# SmartHelmet.net
KiCad netlist of a schematic drawn in Altium Designer
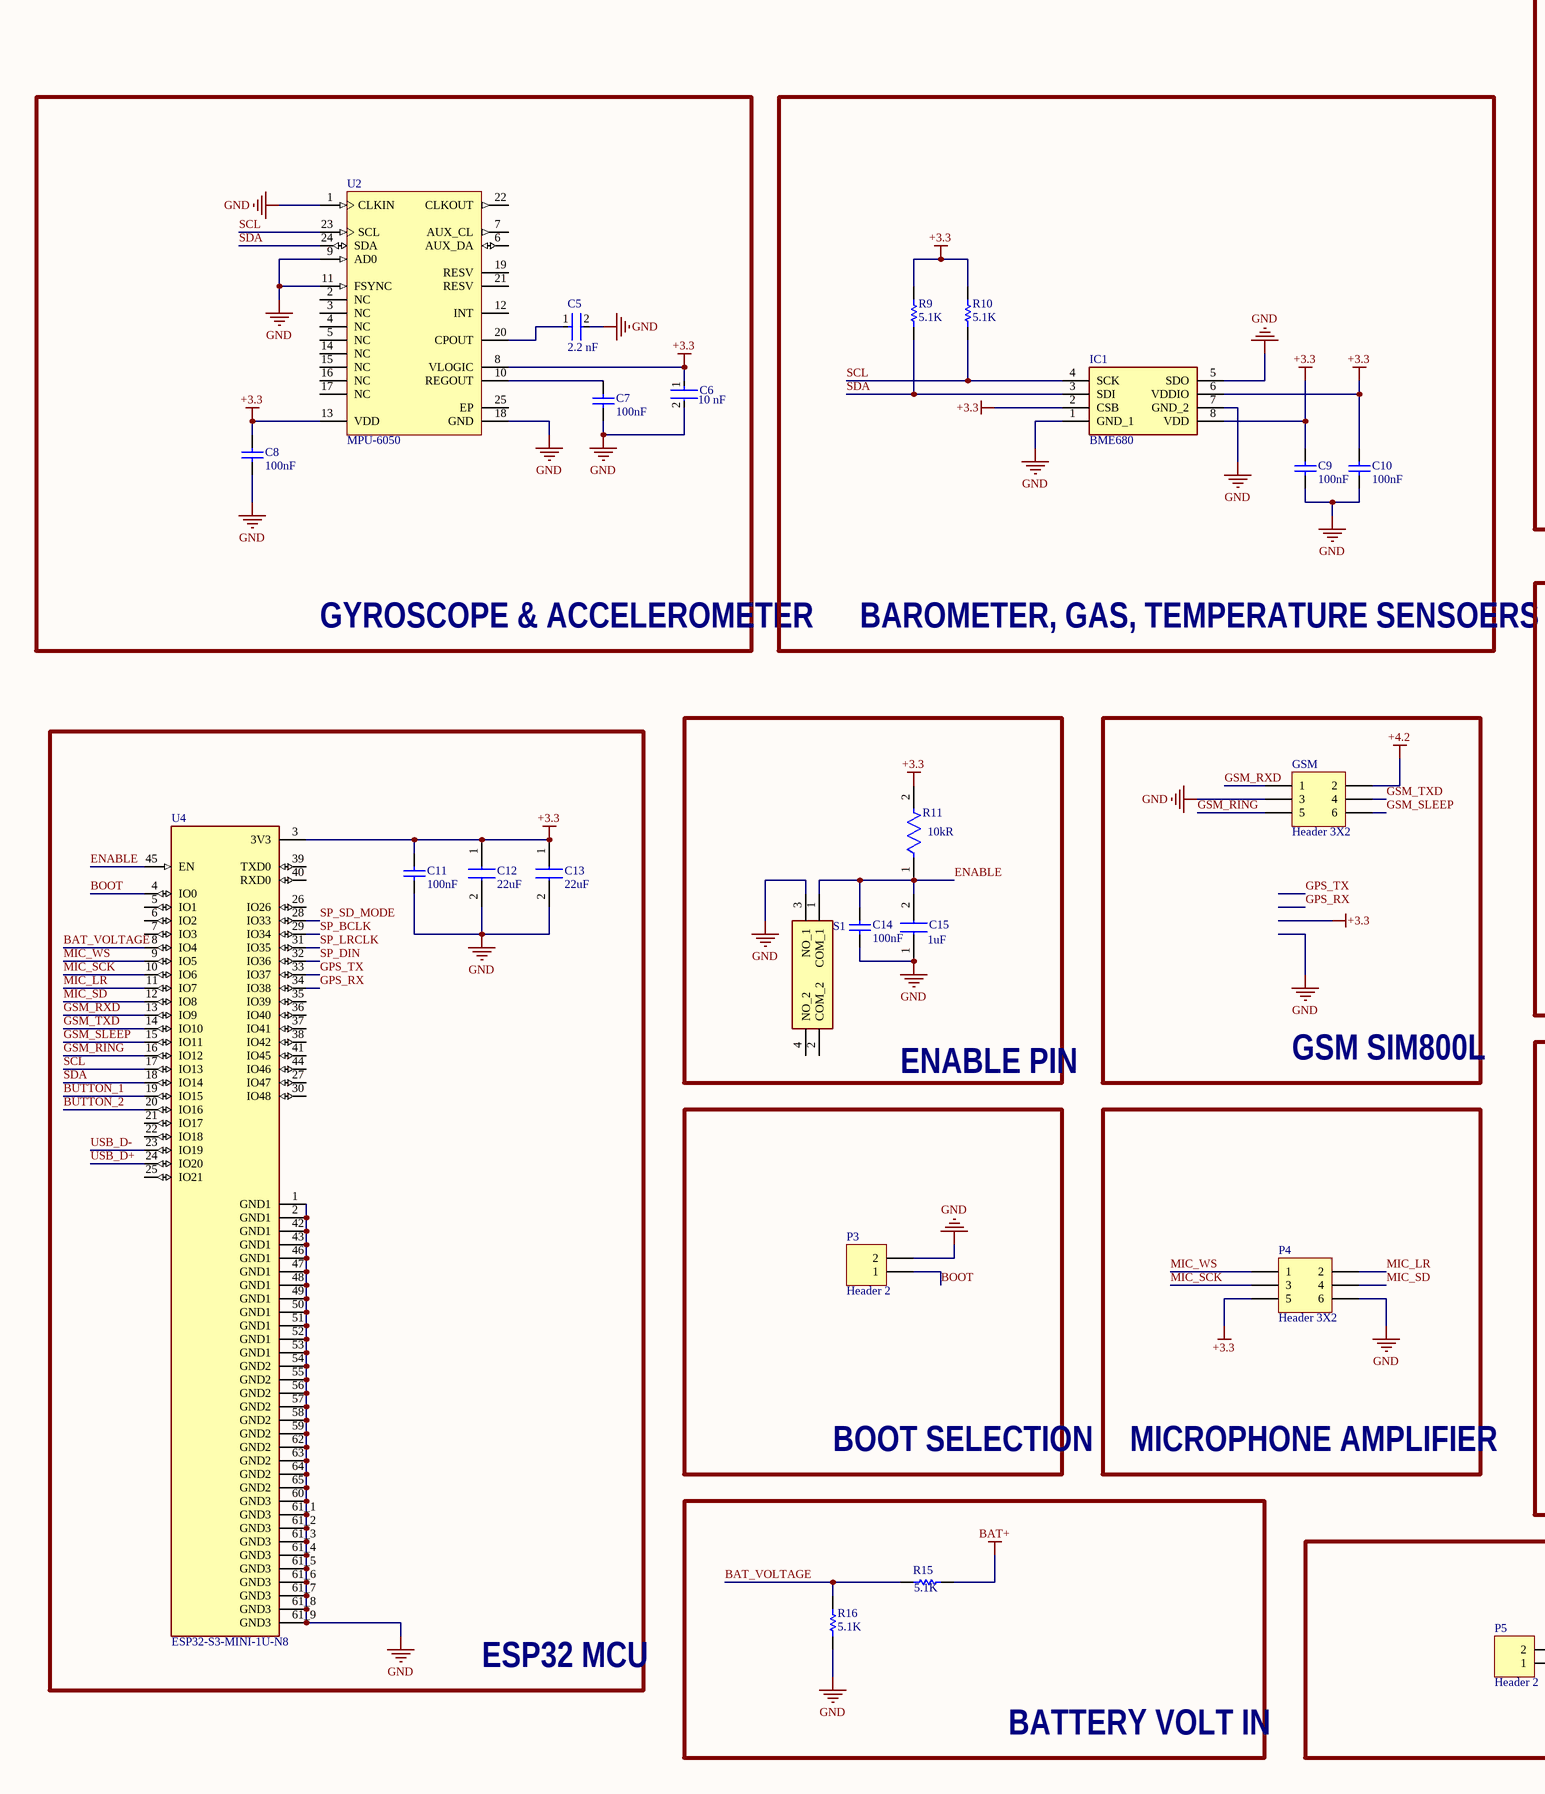
[diagram p0: SmartHelmet.SchDoc, left]
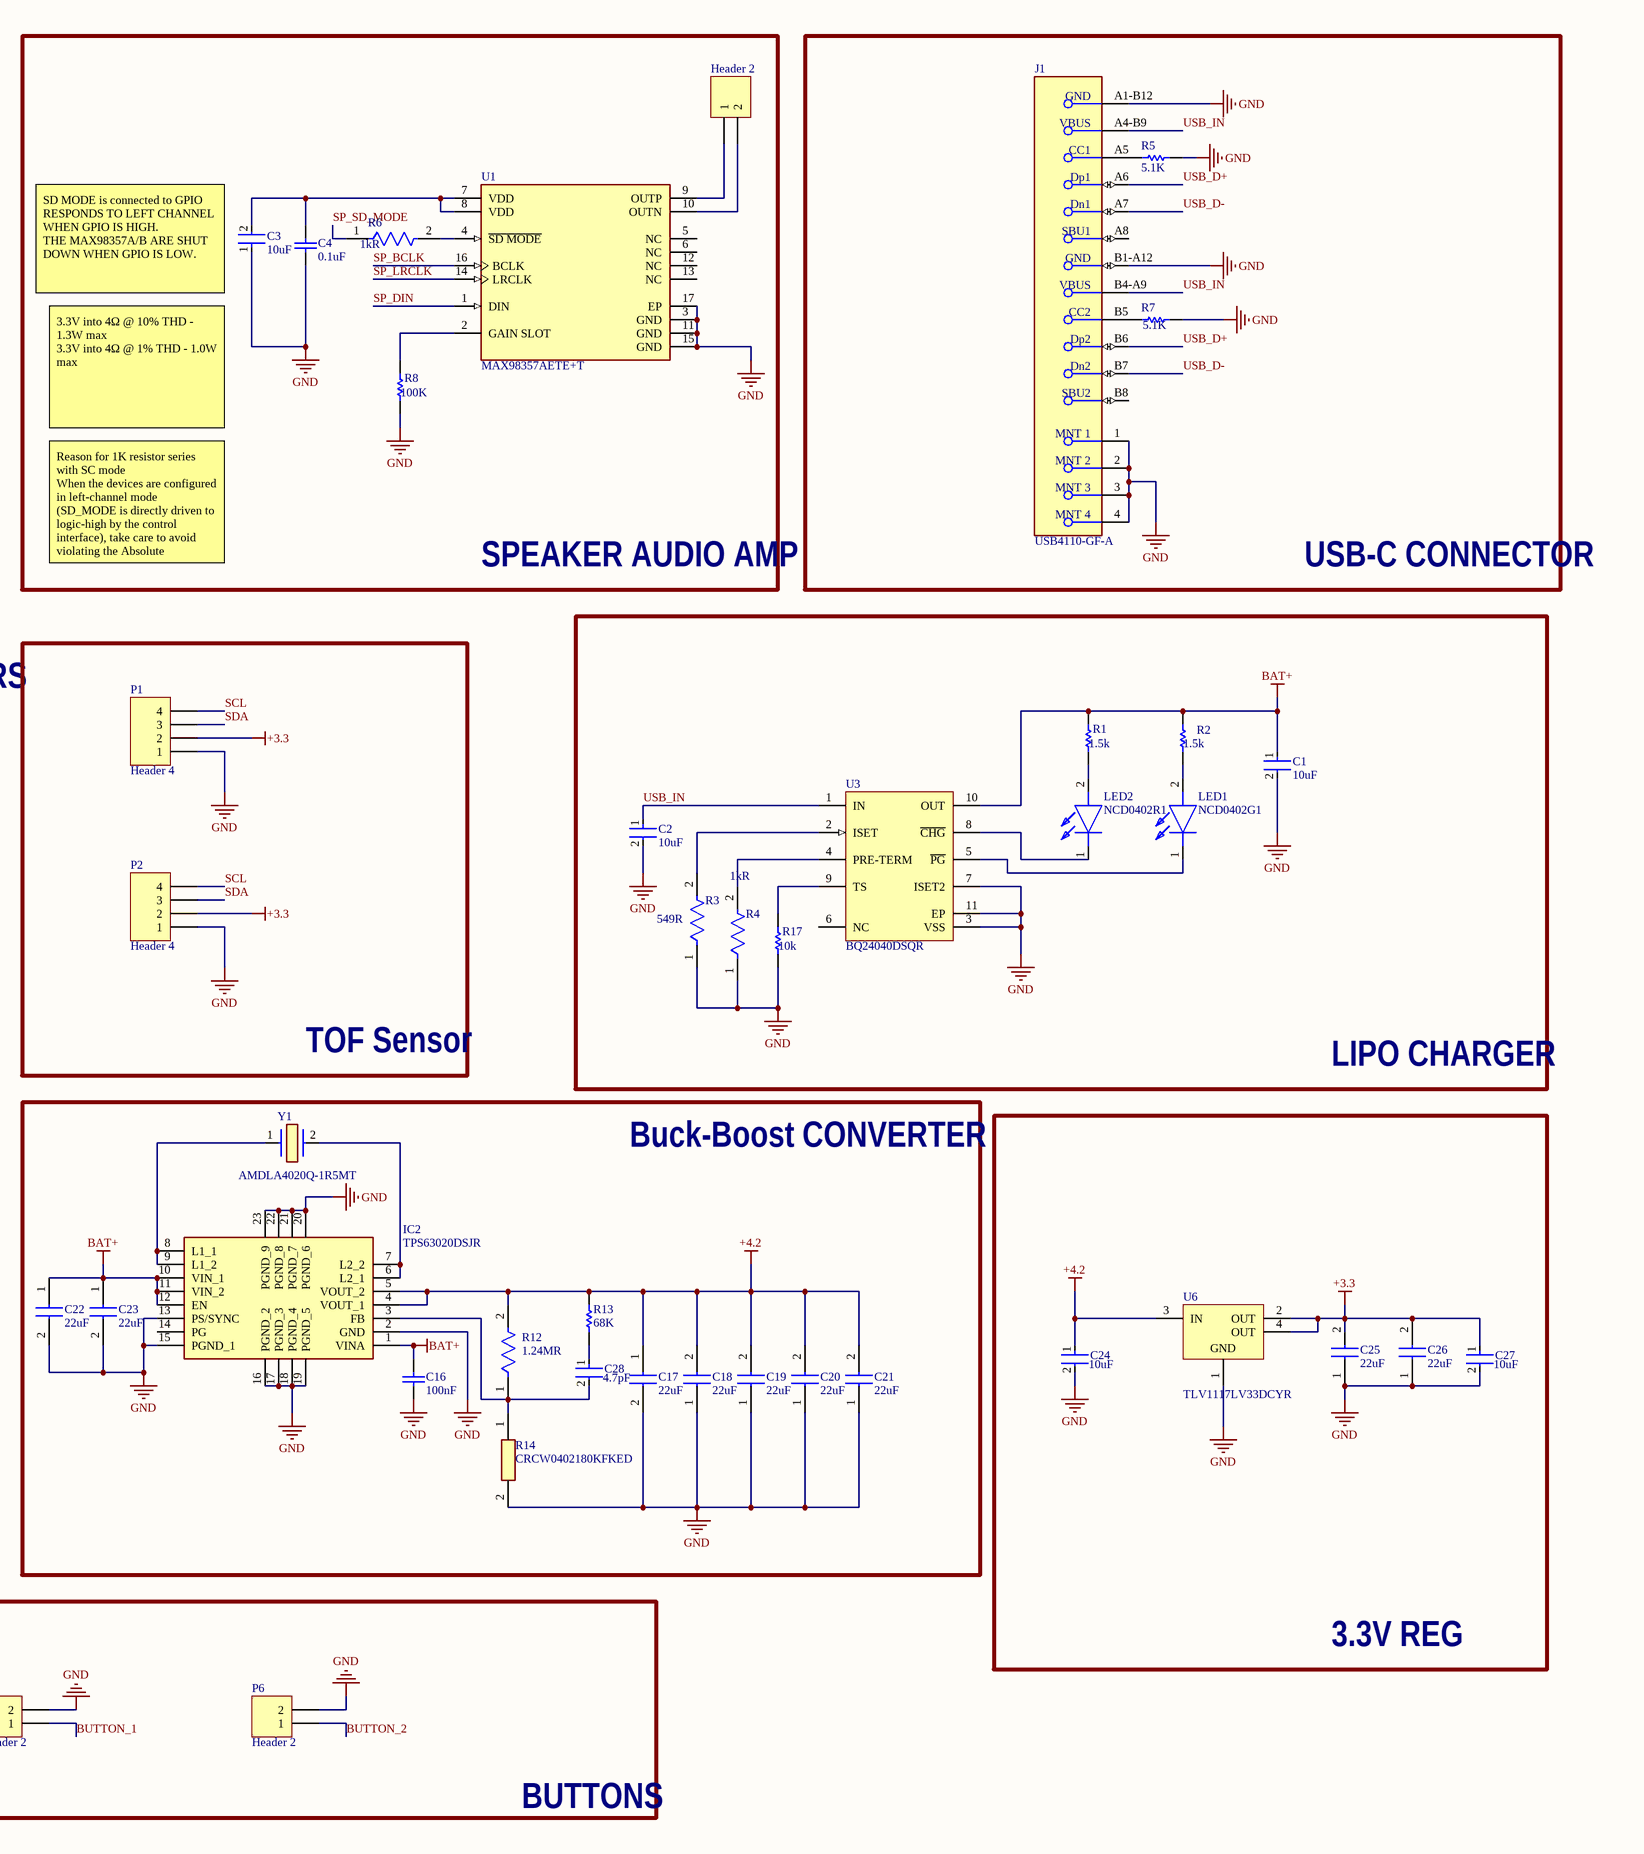
[diagram p1: SmartHelmet.SchDoc, right]

(export (version "E")
  (design (tool "Eeschema 10.0.6"))
  (components
    (comp (ref "C1")
      (value "CL05A106MP5NUNC")
      (footprint "FP-CL05A106MP5NUNC-MFG")
      (description "CAP CER 10UF 10V X5R 0402")
      (fields
        (field (name "OCTOPART") "https://octopart.com/cl05a106mp5nunc-samsung-22457395")
        (field (name "TOLERANCE") "20%")
        (field (name "CAPACITANCE") "10uF")
      )
      (libsource (lib "Altium Content Vault") (part "b4654b650e69147ec39a6b967a45e02"))
    )
    (comp (ref "C2")
      (value "CL05A106MP5NUNC")
      (footprint "FP-CL05A106MP5NUNC-MFG")
      (description "CAP CER 10UF 10V X5R 0402")
      (fields
        (field (name "OCTOPART") "https://octopart.com/cl05a106mp5nunc-samsung-22457395")
        (field (name "TOLERANCE") "20%")
        (field (name "CAPACITANCE") "10uF")
      )
      (libsource (lib "Altium Content Vault") (part "b4654b650e69147ec39a6b967a45e02"))
    )
    (comp (ref "C3")
      (value "CL05A106MP5NUNC")
      (footprint "FP-CL05A106MP5NUNC-MFG")
      (description "CAP CER 10UF 10V X5R 0402")
      (fields
        (field (name "OCTOPART") "https://octopart.com/cl05a106mp5nunc-samsung-22457395")
        (field (name "TOLERANCE") "20%")
        (field (name "CAPACITANCE") "10uF")
      )
      (libsource (lib "Altium Content Vault") (part "b4654b650e69147ec39a6b967a45e02"))
    )
    (comp (ref "C4")
      (value "CL05B104KO5NNNC")
      (footprint "CAPC1050X55X23ML05T13")
      (description "Chip Capacitor, 100 nF, +/- 10%, 16 V, -55 to 125 degC, 0402 (1005 Metric), RoHS, Tape and Reel")
      (fields (field (name "MANUFACTURER") "Samsung Electro-Mechanics") (field (name "CAPACITANCE") "0.1uF"))
      (libsource (lib "Altium Content Vault") (part "CAP-NP-2"))
    )
    (comp (ref "C5")
      (value "CC0402KRX7R9BB222")
      (footprint "FP-CC0402-MFG")
      (description "CAP CER 2200PF 50V X7R 0402")
      (fields
        (field (name "TOLERANCE") "0.1")
        (field (name "OCTOPART") "https://octopart.com/cc0402krx7r9bb222-yageo-39467642")
        (field (name "CAPACITANCE") "2.2 nF")
      )
      (libsource (lib "Altium Content Vault") (part "11868f565c42a9108669ba33697ecf6"))
    )
    (comp (ref "C6")
      (value "CC0402KRX7R9BB103")
      (footprint "FP-CC0402-MFG")
      (description "CAP CER 10000PF 50V X7R 0402")
      (fields
        (field (name "OCTOPART") "https://octopart.com/cc0402krx7r9bb103-yageo-8376513")
        (field (name "CAPACITANCE") "10 nF")
        (field (name "MANUFACTURER") "YAGEO")
      )
      (libsource (lib "Altium Content Vault") (part "11868f565c42a9108669ba33697ecf6"))
    )
    (comp (ref "C7")
      (value "CL05B104KO5NNNC")
      (footprint "CAPC1050X55X23ML05T13")
      (description "Chip Capacitor, 100 nF, +/- 10%, 16 V, -55 to 125 degC, 0402 (1005 Metric), RoHS, Tape and Reel")
      (fields (field (name "MANUFACTURER") "Samsung Electro-Mechanics") (field (name "CAPACITANCE") "100nF"))
      (libsource (lib "Altium Content Vault") (part "CAP-NP-2"))
    )
    (comp (ref "C8")
      (value "CL05B104KO5NNNC")
      (footprint "CAPC1050X55X23ML05T13")
      (description "Chip Capacitor, 100 nF, +/- 10%, 16 V, -55 to 125 degC, 0402 (1005 Metric), RoHS, Tape and Reel")
      (fields (field (name "MANUFACTURER") "Samsung Electro-Mechanics") (field (name "CAPACITANCE") "100nF"))
      (libsource (lib "Altium Content Vault") (part "CAP-NP-2"))
    )
    (comp (ref "C9")
      (value "CL05B104KO5NNNC")
      (footprint "CAPC1050X55X23ML05T13")
      (description "Chip Capacitor, 100 nF, +/- 10%, 16 V, -55 to 125 degC, 0402 (1005 Metric), RoHS, Tape and Reel")
      (fields (field (name "MANUFACTURER") "Samsung Electro-Mechanics") (field (name "CAPACITANCE") "100nF"))
      (libsource (lib "Altium Content Vault") (part "CAP-NP-2"))
    )
    (comp (ref "C10")
      (value "CL05B104KO5NNNC")
      (footprint "CAPC1050X55X23ML05T13")
      (description "Chip Capacitor, 100 nF, +/- 10%, 16 V, -55 to 125 degC, 0402 (1005 Metric), RoHS, Tape and Reel")
      (fields (field (name "MANUFACTURER") "Samsung Electro-Mechanics") (field (name "CAPACITANCE") "100nF"))
      (libsource (lib "Altium Content Vault") (part "CAP-NP-2"))
    )
    (comp (ref "C11")
      (value "CL05B104KO5NNNC")
      (footprint "CAPC1050X55X23ML05T13")
      (description "Chip Capacitor, 100 nF, +/- 10%, 16 V, -55 to 125 degC, 0402 (1005 Metric), RoHS, Tape and Reel")
      (fields (field (name "MANUFACTURER") "Samsung Electro-Mechanics") (field (name "CAPACITANCE") "100nF"))
      (libsource (lib "Altium Content Vault") (part "CAP-NP-2"))
    )
    (comp (ref "C12")
      (value "22uF")
      (footprint "SamacSys:CAPC1608X105N")
      (description "Capacitor")
      (fields
        (field (name "MANUFACTURER_PART_NUMBER") "CL10A226MP8NUNE")
        (field (name "MOUSER PART NUMBER") "187-CL10A226MP8NUNE")
      )
      (libsource (lib "*") (part "CL10A226MP8NUNE"))
    )
    (comp (ref "C13")
      (value "22uF")
      (footprint "SamacSys:CAPC1608X105N")
      (description "Capacitor")
      (fields
        (field (name "MANUFACTURER_PART_NUMBER") "CL10A226MP8NUNE")
        (field (name "MOUSER PART NUMBER") "187-CL10A226MP8NUNE")
      )
      (libsource (lib "*") (part "CL10A226MP8NUNE"))
    )
    (comp (ref "C14")
      (value "CL05B104KO5NNNC")
      (footprint "CAPC1050X55X23ML05T13")
      (description "Chip Capacitor, 100 nF, +/- 10%, 16 V, -55 to 125 degC, 0402 (1005 Metric), RoHS, Tape and Reel")
      (fields (field (name "MANUFACTURER") "Samsung Electro-Mechanics") (field (name "CAPACITANCE") "100nF"))
      (libsource (lib "Altium Content Vault") (part "CAP-NP-2"))
    )
    (comp (ref "C15")
      (value "GRM155C71C105KE11J")
      (footprint "SamacSys:CAPC1005X55N")
      (description "Capacitor")
      (fields (field (name "MOUSER PART NUMBER") "81-GRM155C71C105KE11") (field (name "CAPACITANCE") "1uF"))
      (libsource (lib "*") (part "GRM155C71C105KE11J"))
    )
    (comp (ref "C16")
      (value "CL05B104KO5NNNC")
      (footprint "CAPC1050X55X23ML05T13")
      (description "Chip Capacitor, 100 nF, +/- 10%, 16 V, -55 to 125 degC, 0402 (1005 Metric), RoHS, Tape and Reel")
      (fields (field (name "MANUFACTURER") "Samsung Electro-Mechanics") (field (name "CAPACITANCE") "100nF"))
      (libsource (lib "Altium Content Vault") (part "CAP-NP-2"))
    )
    (comp (ref "C17")
      (value "22uF")
      (footprint "SamacSys:CAPC1608X105N")
      (description "Capacitor")
      (fields
        (field (name "MANUFACTURER_PART_NUMBER") "CL10A226MP8NUNE")
        (field (name "MOUSER PART NUMBER") "187-CL10A226MP8NUNE")
      )
      (libsource (lib "*") (part "CL10A226MP8NUNE"))
    )
    (comp (ref "C18")
      (value "22uF")
      (footprint "SamacSys:CAPC1608X105N")
      (description "Capacitor")
      (fields
        (field (name "MANUFACTURER_PART_NUMBER") "CL10A226MP8NUNE")
        (field (name "MOUSER PART NUMBER") "187-CL10A226MP8NUNE")
      )
      (libsource (lib "*") (part "CL10A226MP8NUNE"))
    )
    (comp (ref "C19")
      (value "22uF")
      (footprint "SamacSys:CAPC1608X105N")
      (description "Capacitor")
      (fields
        (field (name "MANUFACTURER_PART_NUMBER") "CL10A226MP8NUNE")
        (field (name "MOUSER PART NUMBER") "187-CL10A226MP8NUNE")
      )
      (libsource (lib "*") (part "CL10A226MP8NUNE"))
    )
    (comp (ref "C20")
      (value "22uF")
      (footprint "SamacSys:CAPC1608X105N")
      (description "Capacitor")
      (fields
        (field (name "MANUFACTURER_PART_NUMBER") "CL10A226MP8NUNE")
        (field (name "MOUSER PART NUMBER") "187-CL10A226MP8NUNE")
      )
      (libsource (lib "*") (part "CL10A226MP8NUNE"))
    )
    (comp (ref "C21")
      (value "22uF")
      (footprint "SamacSys:CAPC1608X105N")
      (description "Capacitor")
      (fields
        (field (name "MANUFACTURER_PART_NUMBER") "CL10A226MP8NUNE")
        (field (name "MOUSER PART NUMBER") "187-CL10A226MP8NUNE")
      )
      (libsource (lib "*") (part "CL10A226MP8NUNE"))
    )
    (comp (ref "C22")
      (value "22uF")
      (footprint "SamacSys:CAPC1608X105N")
      (description "Capacitor")
      (fields
        (field (name "MANUFACTURER_PART_NUMBER") "CL10A226MP8NUNE")
        (field (name "MOUSER PART NUMBER") "187-CL10A226MP8NUNE")
      )
      (libsource (lib "*") (part "CL10A226MP8NUNE"))
    )
    (comp (ref "C23")
      (value "22uF")
      (footprint "SamacSys:CAPC1608X105N")
      (description "Capacitor")
      (fields
        (field (name "MANUFACTURER_PART_NUMBER") "CL10A226MP8NUNE")
        (field (name "MOUSER PART NUMBER") "187-CL10A226MP8NUNE")
      )
      (libsource (lib "*") (part "CL10A226MP8NUNE"))
    )
    (comp (ref "C24")
      (value "CL05A106MP5NUNC")
      (footprint "FP-CL05A106MP5NUNC-MFG")
      (description "CAP CER 10UF 10V X5R 0402")
      (fields
        (field (name "OCTOPART") "https://octopart.com/cl05a106mp5nunc-samsung-22457395")
        (field (name "TOLERANCE") "20%")
        (field (name "CAPACITANCE") "10uF")
      )
      (libsource (lib "Altium Content Vault") (part "b4654b650e69147ec39a6b967a45e02"))
    )
    (comp (ref "C25")
      (value "22uF")
      (footprint "SamacSys:CAPC1608X105N")
      (description "Capacitor")
      (fields
        (field (name "MANUFACTURER_PART_NUMBER") "CL10A226MP8NUNE")
        (field (name "MOUSER PART NUMBER") "187-CL10A226MP8NUNE")
      )
      (libsource (lib "*") (part "CL10A226MP8NUNE"))
    )
    (comp (ref "C26")
      (value "22uF")
      (footprint "SamacSys:CAPC1608X105N")
      (description "Capacitor")
      (fields
        (field (name "MANUFACTURER_PART_NUMBER") "CL10A226MP8NUNE")
        (field (name "MOUSER PART NUMBER") "187-CL10A226MP8NUNE")
      )
      (libsource (lib "*") (part "CL10A226MP8NUNE"))
    )
    (comp (ref "C27")
      (value "CL05A106MP5NUNC")
      (footprint "FP-CL05A106MP5NUNC-MFG")
      (description "CAP CER 10UF 10V X5R 0402")
      (fields
        (field (name "OCTOPART") "https://octopart.com/cl05a106mp5nunc-samsung-22457395")
        (field (name "TOLERANCE") "20%")
        (field (name "CAPACITANCE") "10uF")
      )
      (libsource (lib "Altium Content Vault") (part "b4654b650e69147ec39a6b967a45e02"))
    )
    (comp (ref "C28")
      (value "GCQ1555C1H4R7BB01D")
      (footprint "FP-GCQ155-0_05-IPC_B")
      (description "High Q Ceramic Capacitor for Automotive 4.7pF ±0.1pF 50VDC C0G 0402 Paper T/R")
      (fields (field (name "CAPACITANCE") "4.7pF"))
      (libsource (lib "Altium Content Vault") (part "02cd4be3c70576c341d710602a673aa"))
    )
    (comp (ref "GSM")
      (value "Header 3X2")
      (footprint "HDR2X3")
      (description "Header, 3-Pin, Dual row")
      (fields (field (name "PUBLISHER") "Altium Limited"))
      (libsource (lib "Miscellaneous Connectors") (part "Header 3X2"))
    )
    (comp (ref "IC1")
      (value "BME680")
      (footprint "SamacSys:BME680")
      (description "Integrated Circuit")
      (fields (field (name "MOUSER PART NUMBER") "262-BME680"))
      (libsource (lib "SamacSys") (part "BME680"))
    )
    (comp (ref "IC2")
      (value "TPS63020DSJR")
      (footprint "TPS63020DSJR")
      (description "Integrated Circuit")
      (fields (field (name "MOUSER PART NUMBER") "595-TPS63020DSJR"))
      (libsource (lib "SamacSys") (part "TPS63020DSJR"))
    )
    (comp (ref "J1")
      (value "USB4110-GF-A")
      (footprint "FP-USB4110-GF-A-MFG")
      (description "CONN USB 2.0 TYPE-C R/A SMT")
      (fields
        (field (name "OCTOPART") "https://octopart.com/usb4110-gf-a-gct-103941985")
        (field (name "MANUFACTURER") "GCT")
      )
      (libsource (lib "Altium Content Vault") (part "e23f2b38bb3c3f98e683ebab9ede730"))
    )
    (comp (ref "LED1")
      (value "NCD0402G1")
      (footprint "NCD0402R1")
      (description "LED  NCD0402G1")
      (fields (field (name "MANUFACTURER_PART_NUMBER") "NCD0402R1"))
      (libsource (lib "SamacSys") (part "NCD0402R1"))
    )
    (comp (ref "LED2")
      (value "NCD0402R1")
      (footprint "NCD0402R1")
      (description "LED")
      (libsource (lib "SamacSys") (part "NCD0402R1"))
    )
    (comp (ref "P1")
      (value "Header 4")
      (footprint "HDR1X4")
      (description "Header, 4-Pin")
      (fields (field (name "PUBLISHER") "Altium Limited"))
      (libsource (lib "Miscellaneous Connectors") (part "Header 4"))
    )
    (comp (ref "P2")
      (value "Header 4")
      (footprint "HDR1X4")
      (description "Header, 4-Pin")
      (fields (field (name "PUBLISHER") "Altium Limited"))
      (libsource (lib "Miscellaneous Connectors") (part "Header 4"))
    )
    (comp (ref "P3")
      (value "Header 2")
      (footprint "HDR1X2")
      (description "Header, 2-Pin")
      (fields (field (name "PUBLISHER") "Altium Limited"))
      (libsource (lib "") (part "Header 2_1"))
    )
    (comp (ref "P4")
      (value "Header 3X2")
      (footprint "HDR2X3")
      (description "Header, 3-Pin, Dual row")
      (fields (field (name "PUBLISHER") "Altium Limited"))
      (libsource (lib "Miscellaneous Connectors") (part "Header 3X2"))
    )
    (comp (ref "P5")
      (value "Header 2")
      (footprint "HDR1X2")
      (description "Header, 2-Pin")
      (fields (field (name "PUBLISHER") "Altium Limited"))
      (libsource (lib "") (part "Header 2_1"))
    )
    (comp (ref "P6")
      (value "Header 2")
      (footprint "HDR1X2")
      (description "Header, 2-Pin")
      (fields (field (name "PUBLISHER") "Altium Limited"))
      (libsource (lib "") (part "Header 2_1"))
    )
    (comp (ref "P7")
      (value "Header 2")
      (footprint "HDR1X2")
      (description "Header, 2-Pin")
      (fields (field (name "PUBLISHER") "Altium Limited"))
      (libsource (lib "Miscellaneous Connectors") (part "Header 2"))
    )
    (comp (ref "R1")
      (value "1.5k")
      (footprint "RESC1005X40X25ML05T10")
      (fields (field (name "MANUFACTURER") "Yageo / Phycomp") (field (name "PART NUMBER") "RC0402FR-071K5L"))
      (libsource (lib "Altium Content Vault") (part "RES"))
    )
    (comp (ref "R2")
      (value "1.5k")
      (footprint "RESC1005X40X25ML05T10")
      (fields (field (name "MANUFACTURER") "Yageo / Phycomp") (field (name "PART NUMBER") "RC0402FR-071K5L"))
      (libsource (lib "Altium Content Vault") (part "RES"))
    )
    (comp (ref "R3")
      (value "AC0402FR-07549RL")
      (footprint "FP-AC0402-IPC_B")
      (description "RES 549Ω ±1% 0.063W 0402")
      (fields (field (name "TOLERANCE") "1%") (field (name "RESISTANCE") "549R"))
      (libsource (lib "Altium Content Vault") (part "1029c3af85768c4190bb7ad29bc67b5"))
    )
    (comp (ref "R4")
      (value "RC0402FR-071KL")
      (footprint "FP-RC0402-0_4-IPC_A")
      (description "RES 1K OHM 1% 1/16W 0402")
      (fields (field (name "TOLERANCE") "1%") (field (name "RESISTANCE") "1kR"))
      (libsource (lib "Altium Content Vault") (part "1029c3af85768c4190bb7ad29bc67b5"))
    )
    (comp (ref "R5")
      (value "RK73H1ETTP5101F")
      (footprint "RESC1005X40X25ML10T10")
      (fields (field (name "MANUFACTURER") "KOA Speer") (field (name "RESISTANCE") "5.1K"))
      (libsource (lib "Altium Content Vault") (part "RES"))
    )
    (comp (ref "R6")
      (value "CRCW04021K00FKED")
      (footprint "FP-CRCW0402-e3-MFG")
      (description "RES Thick Film, 1kΩ, 1%, 0.063W, 100ppm/°C, 0402")
      (fields (field (name "RESISTANCE") "1kR") (field (name "TOLERANCE") "1%"))
      (libsource (lib "Altium Content Vault") (part "1029c3af85768c4190bb7ad29bc67b5"))
    )
    (comp (ref "R7")
      (value "RK73H1ETTP5101F")
      (footprint "RESC1005X40X25ML10T10")
      (fields (field (name "MANUFACTURER") "KOA Speer") (field (name "RESISTANCE") "5.1K"))
      (libsource (lib "Altium Content Vault") (part "RES"))
    )
    (comp (ref "R8")
      (value "RC0402FR-07100KL")
      (footprint "RESC1005X40X25NL05T10")
      (fields (field (name "MANUFACTURER") "Yageo / Phycomp") (field (name "RESISTANCE") "100K"))
      (libsource (lib "Altium Content Vault") (part "RES"))
    )
    (comp (ref "R9")
      (value "RK73H1ETTP5101F")
      (footprint "RESC1005X40X25ML10T10")
      (fields (field (name "MANUFACTURER") "KOA Speer") (field (name "RESISTANCE") "5.1K"))
      (libsource (lib "Altium Content Vault") (part "RES"))
    )
    (comp (ref "R10")
      (value "RK73H1ETTP5101F")
      (footprint "RESC1005X40X25ML10T10")
      (fields (field (name "MANUFACTURER") "KOA Speer") (field (name "RESISTANCE") "5.1K"))
      (libsource (lib "Altium Content Vault") (part "RES"))
    )
    (comp (ref "R11")
      (value "CRCW040210K0FKEE")
      (footprint "FP-CRCW0402-e3-IPC_C")
      (description "RES Thick Film, 10kΩ, 1%, 0.063W, 100ppm/°C, 0402")
      (fields (field (name "RESISTANCE") "10kR") (field (name "TOLERANCE") "1%"))
      (libsource (lib "Altium Content Vault") (part "1029c3af85768c4190bb7ad29bc67b5"))
    )
    (comp (ref "R12")
      (value "CRCW04021M24FKED")
      (footprint "FP-CRCW0402-e3-IPC_C")
      (description "RES Thick Film, 1.24MΩ, 1%, 0.063W, 100ppm/°C, 0402")
      (fields (field (name "RESISTANCE") "1.24MR") (field (name "TOLERANCE") "1%"))
      (libsource (lib "Altium Content Vault") (part "1029c3af85768c4190bb7ad29bc67b5"))
    )
    (comp (ref "R13")
      (value "CRCW040268K0FKED")
      (footprint "RESC1005X40X25LL05T05")
      (fields (field (name "MANUFACTURER") "Vishay Dale") (field (name "RESISTANCE") "68K"))
      (libsource (lib "Altium Content Vault") (part "RES"))
    )
    (comp (ref "R14")
      (value "CRCW0402180KFKED")
      (footprint "RESC1005X40N")
      (description "Resistor")
      (fields (field (name "MOUSER PART NUMBER") "71-CRCW0402180KFKED"))
      (libsource (lib "SamacSys") (part "CRCW0402180KFKED"))
    )
    (comp (ref "R15")
      (value "RK73H1ETTP5101F")
      (footprint "RESC1005X40X25ML10T10")
      (fields (field (name "MANUFACTURER") "KOA Speer") (field (name "RESISTANCE") "5.1K"))
      (libsource (lib "Altium Content Vault") (part "RES"))
    )
    (comp (ref "R16")
      (value "RK73H1ETTP5101F")
      (footprint "RESC1005X40X25ML10T10")
      (fields (field (name "MANUFACTURER") "KOA Speer") (field (name "RESISTANCE") "5.1K"))
      (libsource (lib "Altium Content Vault") (part "RES"))
    )
    (comp (ref "R17")
      (value "10k")
      (footprint "RESC1005X40X25ML05T10")
      (fields (field (name "PART NUMBER") "RC0402FR-0710KL") (field (name "MANUFACTURER") "Yageo / Phycomp"))
      (libsource (lib "Altium Content Vault") (part "RES"))
    )
    (comp (ref "S1")
      (value "PTS526_SK15_SMTR2_LFS")
      (footprint "SamacSys:PTS526SK15SMTR2LFS")
      (description "Switch")
      (fields
        (field (name "MANUFACTURER_PART_NUMBER") "PTS526 SK15 SMTR2 LFS")
        (field (name "MOUSER PART NUMBER") "611-PTS526SK15SMR2L")
      )
      (libsource (lib "*") (part "PTS526_SK15_SMTR2_LFS"))
    )
    (comp (ref "U1")
      (value "MAX98357AETE+T")
      (footprint "FP-T1633-4-MFG")
      (description "IC AMP CLASS D MONO 3.2W 16TQFN")
      (libsource (lib "Altium Content Vault") (part "902df0143a84dfa2dd990dcc5368a09"))
    )
    (comp (ref "U2")
      (value "MPU-6050")
      (footprint "IS-QFN-24_V")
      (fields (field (name "MANUFACTURER") "InvenSense"))
      (libsource (lib "Altium Content Vault") (part "IS-MPU-6050-QFN-24"))
    )
    (comp (ref "U3")
      (value "BQ24040DSQR")
      (footprint "DSQ0010A_V")
      (fields (field (name "MANUFACTURER") "Texas Instruments"))
      (libsource (lib "Altium Content Vault") (part "TI-BQ24040DSQ10-1500X900TP"))
    )
    (comp (ref "U4")
      (value "ESP32-S3-MINI-1U-N8")
      (footprint "XCVR_ESP32-S3-MINI-1U-N8")
      (fields (field (name "MF") "Espressif Systems"))
      (libsource (lib "ESP32-S3-MINI-1U-N8") (part "ESP32-S3-MINI-1U-N8"))
    )
    (comp (ref "U6")
      (value "TLV1117LV33DCYR")
      (footprint "DCY0004A_N")
      (fields (field (name "MANUFACTURER") "Texas Instruments"))
      (libsource (lib "Altium Content Vault") (part "TI-TLV1117LV33DCY4"))
    )
    (comp (ref "Y1")
      (value "AMDLA4020Q-1R5MT")
      (footprint "SamacSys:INDPM4440X200N")
      (description "Crystal or Oscillator")
      (fields (field (name "MOUSER PART NUMBER") "815-AMDLA4020Q-1R5MT"))
      (libsource (lib "*") (part "AMDLA4020Q-1R5MT"))
    )
  )
  (nets
    (net (code "1") (name "+3.3") (class "Default")
      (node (ref "C10") (pin "1") (pinfunction "1_1") (pintype "passive"))
      (node (ref "C11") (pin "2") (pinfunction "2_2") (pintype "passive"))
      (node (ref "C12") (pin "1") (pinfunction "1_1") (pintype "passive"))
      (node (ref "C13") (pin "1") (pinfunction "1_1") (pintype "passive"))
      (node (ref "C25") (pin "2") (pinfunction "2_2") (pintype "passive"))
      (node (ref "C26") (pin "2") (pinfunction "2_2") (pintype "passive"))
      (node (ref "C27") (pin "1") (pinfunction "1_1") (pintype "passive"))
      (node (ref "C6") (pin "1") (pinfunction "1_1") (pintype "passive"))
      (node (ref "C8") (pin "2") (pinfunction "2_2") (pintype "passive"))
      (node (ref "C9") (pin "1") (pinfunction "1_1") (pintype "passive"))
      (node (ref "IC1") (pin "2") (pinfunction "CSB_2") (pintype "passive"))
      (node (ref "IC1") (pin "6") (pinfunction "VDDIO_6") (pintype "passive"))
      (node (ref "IC1") (pin "8") (pinfunction "VDD_8") (pintype "passive"))
      (node (ref "P1") (pin "2") (pinfunction "2_2") (pintype "passive"))
      (node (ref "P2") (pin "2") (pinfunction "2_2") (pintype "passive"))
      (node (ref "P4") (pin "5") (pinfunction "5_5") (pintype "passive"))
      (node (ref "R10") (pin "2") (pinfunction "2_2") (pintype "passive"))
      (node (ref "R11") (pin "2") (pinfunction "2_2") (pintype "passive"))
      (node (ref "R9") (pin "2") (pinfunction "2_2") (pintype "passive"))
      (node (ref "U2") (pin "13") (pinfunction "VDD_13") (pintype "power_in"))
      (node (ref "U2") (pin "8") (pinfunction "VLOGIC_8") (pintype "power_in"))
      (node (ref "U4") (pin "3") (pinfunction "3V3_3") (pintype "power_in"))
      (node (ref "U6") (pin "2") (pinfunction "OUT_2") (pintype "power_in"))
      (node (ref "U6") (pin "4") (pinfunction "OUT_4") (pintype "power_in"))
    )
    (net (code "2") (name "+4.2") (class "Default")
      (node (ref "C17") (pin "1") (pinfunction "1_1") (pintype "passive"))
      (node (ref "C18") (pin "2") (pinfunction "2_2") (pintype "passive"))
      (node (ref "C19") (pin "2") (pinfunction "2_2") (pintype "passive"))
      (node (ref "C20") (pin "2") (pinfunction "2_2") (pintype "passive"))
      (node (ref "C21") (pin "2") (pinfunction "2_2") (pintype "passive"))
      (node (ref "C24") (pin "1") (pinfunction "1_1") (pintype "passive"))
      (node (ref "GSM") (pin "2") (pinfunction "2_2") (pintype "passive"))
      (node (ref "IC2") (pin "4") (pinfunction "VOUT_1_4") (pintype "passive"))
      (node (ref "IC2") (pin "5") (pinfunction "VOUT_2_5") (pintype "passive"))
      (node (ref "R12") (pin "2") (pinfunction "2_2") (pintype "passive"))
      (node (ref "R13") (pin "2") (pinfunction "2_2") (pintype "passive"))
      (node (ref "U6") (pin "3") (pinfunction "IN_3") (pintype "power_in"))
    )
    (net (code "3") (name "/BAT_VOLTAGE") (class "Default")
      (node (ref "R15") (pin "1") (pinfunction "1_1") (pintype "passive"))
      (node (ref "R16") (pin "2") (pinfunction "2_2") (pintype "passive"))
      (node (ref "U4") (pin "8") (pinfunction "IO4_8") (pintype "bidirectional"))
    )
    (net (code "4") (name "/BOOT") (class "Default")
      (node (ref "P3") (pin "1") (pinfunction "1_1") (pintype "passive"))
      (node (ref "U4") (pin "4") (pinfunction "IO0_4") (pintype "bidirectional"))
    )
    (net (code "5") (name "/BUTTON_1") (class "Default")
      (node (ref "P5") (pin "1") (pinfunction "1_1") (pintype "passive"))
      (node (ref "U4") (pin "19") (pinfunction "IO15_19") (pintype "bidirectional"))
    )
    (net (code "6") (name "/BUTTON_2") (class "Default")
      (node (ref "P6") (pin "1") (pinfunction "1_1") (pintype "passive"))
      (node (ref "U4") (pin "20") (pinfunction "IO16_20") (pintype "bidirectional"))
    )
    (net (code "7") (name "/ENABLE") (class "Default")
      (node (ref "C14") (pin "1") (pinfunction "1_1") (pintype "passive"))
      (node (ref "C15") (pin "2") (pinfunction "2_2") (pintype "passive"))
      (node (ref "R11") (pin "1") (pinfunction "1_1") (pintype "passive"))
      (node (ref "S1") (pin "1") (pinfunction "COM_1_1") (pintype "passive"))
      (node (ref "U4") (pin "45") (pinfunction "EN_45") (pintype "input"))
    )
    (net (code "8") (name "/GPS_RX") (class "Default")
      (node (ref "U4") (pin "34") (pinfunction "IO38_34") (pintype "bidirectional"))
    )
    (net (code "9") (name "/GPS_TX") (class "Default")
      (node (ref "U4") (pin "33") (pinfunction "IO37_33") (pintype "bidirectional"))
    )
    (net (code "10") (name "/GSM_RING") (class "Default")
      (node (ref "GSM") (pin "5") (pinfunction "5_5") (pintype "passive"))
      (node (ref "U4") (pin "16") (pinfunction "IO12_16") (pintype "bidirectional"))
    )
    (net (code "11") (name "/GSM_RXD") (class "Default")
      (node (ref "GSM") (pin "1") (pinfunction "1_1") (pintype "passive"))
      (node (ref "U4") (pin "13") (pinfunction "IO9_13") (pintype "bidirectional"))
    )
    (net (code "12") (name "/GSM_SLEEP") (class "Default")
      (node (ref "GSM") (pin "6") (pinfunction "6_6") (pintype "passive"))
      (node (ref "U4") (pin "15") (pinfunction "IO11_15") (pintype "bidirectional"))
    )
    (net (code "13") (name "/GSM_TXD") (class "Default")
      (node (ref "GSM") (pin "4") (pinfunction "4_4") (pintype "passive"))
      (node (ref "U4") (pin "14") (pinfunction "IO10_14") (pintype "bidirectional"))
    )
    (net (code "14") (name "/MIC_LR") (class "Default")
      (node (ref "P4") (pin "2") (pinfunction "2_2") (pintype "passive"))
      (node (ref "U4") (pin "11") (pinfunction "IO7_11") (pintype "bidirectional"))
    )
    (net (code "15") (name "/MIC_SCK") (class "Default")
      (node (ref "P4") (pin "3") (pinfunction "3_3") (pintype "passive"))
      (node (ref "U4") (pin "10") (pinfunction "IO6_10") (pintype "bidirectional"))
    )
    (net (code "16") (name "/MIC_SD") (class "Default")
      (node (ref "P4") (pin "4") (pinfunction "4_4") (pintype "passive"))
      (node (ref "U4") (pin "12") (pinfunction "IO8_12") (pintype "bidirectional"))
    )
    (net (code "17") (name "/MIC_WS") (class "Default")
      (node (ref "P4") (pin "1") (pinfunction "1_1") (pintype "passive"))
      (node (ref "U4") (pin "9") (pinfunction "IO5_9") (pintype "bidirectional"))
    )
    (net (code "18") (name "/SCL") (class "Default")
      (node (ref "IC1") (pin "4") (pinfunction "SCK_4") (pintype "passive"))
      (node (ref "P1") (pin "4") (pinfunction "4_4") (pintype "passive"))
      (node (ref "P2") (pin "4") (pinfunction "4_4") (pintype "passive"))
      (node (ref "R10") (pin "1") (pinfunction "1_1") (pintype "passive"))
      (node (ref "U2") (pin "23") (pinfunction "SCL_23") (pintype "input"))
      (node (ref "U4") (pin "17") (pinfunction "IO13_17") (pintype "bidirectional"))
    )
    (net (code "19") (name "/SDA") (class "Default")
      (node (ref "IC1") (pin "3") (pinfunction "SDI_3") (pintype "passive"))
      (node (ref "P1") (pin "3") (pinfunction "3_3") (pintype "passive"))
      (node (ref "P2") (pin "3") (pinfunction "3_3") (pintype "passive"))
      (node (ref "R9") (pin "1") (pinfunction "1_1") (pintype "passive"))
      (node (ref "U2") (pin "24") (pinfunction "SDA_24") (pintype "bidirectional"))
      (node (ref "U4") (pin "18") (pinfunction "IO14_18") (pintype "bidirectional"))
    )
    (net (code "20") (name "/SP_BCLK") (class "Default")
      (node (ref "U1") (pin "16") (pinfunction "BCLK_16") (pintype "input"))
      (node (ref "U4") (pin "29") (pinfunction "IO34_29") (pintype "bidirectional"))
    )
    (net (code "21") (name "/SP_DIN") (class "Default")
      (node (ref "U1") (pin "1") (pinfunction "DIN_1") (pintype "input"))
      (node (ref "U4") (pin "32") (pinfunction "IO36_32") (pintype "bidirectional"))
    )
    (net (code "22") (name "/SP_LRCLK") (class "Default")
      (node (ref "U1") (pin "14") (pinfunction "LRCLK_14") (pintype "input"))
      (node (ref "U4") (pin "31") (pinfunction "IO35_31") (pintype "bidirectional"))
    )
    (net (code "23") (name "/SP_SD_MODE") (class "Default")
      (node (ref "R6") (pin "1") (pinfunction "1_1") (pintype "passive"))
      (node (ref "U4") (pin "28") (pinfunction "IO33_28") (pintype "bidirectional"))
    )
    (net (code "24") (name "/USB_D+") (class "Default")
      (node (ref "J1") (pin "A6") (pinfunction "Dp1_A6") (pintype "bidirectional"))
      (node (ref "J1") (pin "B6") (pinfunction "Dp2_B6") (pintype "bidirectional"))
      (node (ref "U4") (pin "24") (pinfunction "IO20_24") (pintype "bidirectional"))
    )
    (net (code "25") (name "/USB_D-") (class "Default")
      (node (ref "J1") (pin "A7") (pinfunction "Dn1_A7") (pintype "bidirectional"))
      (node (ref "J1") (pin "B7") (pinfunction "Dn2_B7") (pintype "bidirectional"))
      (node (ref "U4") (pin "23") (pinfunction "IO19_23") (pintype "bidirectional"))
    )
    (net (code "26") (name "/USB_IN") (class "Default")
      (node (ref "C2") (pin "1") (pinfunction "1_1") (pintype "passive"))
      (node (ref "J1") (pin "A4-B9") (pinfunction "VBUS_A4-B9") (pintype "power_in"))
      (node (ref "J1") (pin "B4-A9") (pinfunction "VBUS_B4-A9") (pintype "power_in"))
      (node (ref "U3") (pin "1") (pinfunction "IN_1") (pintype "power_in"))
    )
    (net (code "27") (name "BAT+") (class "Default")
      (node (ref "C1") (pin "1") (pinfunction "1_1") (pintype "passive"))
      (node (ref "C16") (pin "2") (pinfunction "2_2") (pintype "passive"))
      (node (ref "C22") (pin "1") (pinfunction "1_1") (pintype "passive"))
      (node (ref "C23") (pin "1") (pinfunction "1_1") (pintype "passive"))
      (node (ref "IC2") (pin "1") (pinfunction "VINA_1") (pintype "passive"))
      (node (ref "IC2") (pin "10") (pinfunction "VIN_1_10") (pintype "passive"))
      (node (ref "IC2") (pin "11") (pinfunction "VIN_2_11") (pintype "passive"))
      (node (ref "IC2") (pin "12") (pinfunction "EN_12") (pintype "passive"))
      (node (ref "R1") (pin "2") (pinfunction "2_2") (pintype "passive"))
      (node (ref "R15") (pin "2") (pinfunction "2_2") (pintype "passive"))
      (node (ref "R2") (pin "2") (pinfunction "2_2") (pintype "passive"))
      (node (ref "U3") (pin "10") (pinfunction "OUT_10") (pintype "power_in"))
    )
    (net (code "28") (name "GND") (class "Default")
      (node (ref "C1") (pin "2") (pinfunction "2_2") (pintype "passive"))
      (node (ref "C10") (pin "2") (pinfunction "2_2") (pintype "passive"))
      (node (ref "C11") (pin "1") (pinfunction "1_1") (pintype "passive"))
      (node (ref "C12") (pin "2") (pinfunction "2_2") (pintype "passive"))
      (node (ref "C13") (pin "2") (pinfunction "2_2") (pintype "passive"))
      (node (ref "C14") (pin "2") (pinfunction "2_2") (pintype "passive"))
      (node (ref "C15") (pin "1") (pinfunction "1_1") (pintype "passive"))
      (node (ref "C16") (pin "1") (pinfunction "1_1") (pintype "passive"))
      (node (ref "C17") (pin "2") (pinfunction "2_2") (pintype "passive"))
      (node (ref "C18") (pin "1") (pinfunction "1_1") (pintype "passive"))
      (node (ref "C19") (pin "1") (pinfunction "1_1") (pintype "passive"))
      (node (ref "C2") (pin "2") (pinfunction "2_2") (pintype "passive"))
      (node (ref "C20") (pin "1") (pinfunction "1_1") (pintype "passive"))
      (node (ref "C21") (pin "1") (pinfunction "1_1") (pintype "passive"))
      (node (ref "C22") (pin "2") (pinfunction "2_2") (pintype "passive"))
      (node (ref "C23") (pin "2") (pinfunction "2_2") (pintype "passive"))
      (node (ref "C24") (pin "2") (pinfunction "2_2") (pintype "passive"))
      (node (ref "C25") (pin "1") (pinfunction "1_1") (pintype "passive"))
      (node (ref "C26") (pin "1") (pinfunction "1_1") (pintype "passive"))
      (node (ref "C27") (pin "2") (pinfunction "2_2") (pintype "passive"))
      (node (ref "C3") (pin "1") (pinfunction "1_1") (pintype "passive"))
      (node (ref "C4") (pin "1") (pinfunction "1_1") (pintype "passive"))
      (node (ref "C5") (pin "2") (pinfunction "2_2") (pintype "passive"))
      (node (ref "C6") (pin "2") (pinfunction "2_2") (pintype "passive"))
      (node (ref "C7") (pin "1") (pinfunction "1_1") (pintype "passive"))
      (node (ref "C8") (pin "1") (pinfunction "1_1") (pintype "passive"))
      (node (ref "C9") (pin "2") (pinfunction "2_2") (pintype "passive"))
      (node (ref "GSM") (pin "3") (pinfunction "3_3") (pintype "passive"))
      (node (ref "IC1") (pin "1") (pinfunction "GND_1_1") (pintype "passive"))
      (node (ref "IC1") (pin "5") (pinfunction "SDO_5") (pintype "passive"))
      (node (ref "IC1") (pin "7") (pinfunction "GND_2_7") (pintype "passive"))
      (node (ref "IC2") (pin "13") (pinfunction "PS/SYNC_13") (pintype "passive"))
      (node (ref "IC2") (pin "15") (pinfunction "PGND_1_15") (pintype "passive"))
      (node (ref "IC2") (pin "16") (pinfunction "PGND_2_16") (pintype "passive"))
      (node (ref "IC2") (pin "17") (pinfunction "PGND_3_17") (pintype "passive"))
      (node (ref "IC2") (pin "18") (pinfunction "PGND_4_18") (pintype "passive"))
      (node (ref "IC2") (pin "19") (pinfunction "PGND_5_19") (pintype "passive"))
      (node (ref "IC2") (pin "2") (pinfunction "GND_2") (pintype "passive"))
      (node (ref "IC2") (pin "20") (pinfunction "PGND_6_20") (pintype "passive"))
      (node (ref "IC2") (pin "21") (pinfunction "PGND_7_21") (pintype "passive"))
      (node (ref "IC2") (pin "22") (pinfunction "PGND_8_22") (pintype "passive"))
      (node (ref "IC2") (pin "23") (pinfunction "PGND_9_23") (pintype "passive"))
      (node (ref "J1") (pin "1") (pinfunction "MNT_1_1") (pintype "passive"))
      (node (ref "J1") (pin "2") (pinfunction "MNT_2_2") (pintype "passive"))
      (node (ref "J1") (pin "3") (pinfunction "MNT_3_3") (pintype "passive"))
      (node (ref "J1") (pin "4") (pinfunction "MNT_4_4") (pintype "passive"))
      (node (ref "J1") (pin "A1-B12") (pinfunction "GND_A1-B12") (pintype "passive"))
      (node (ref "J1") (pin "B1-A12") (pinfunction "GND_B1-A12") (pintype "bidirectional"))
      (node (ref "P1") (pin "1") (pinfunction "1_1") (pintype "passive"))
      (node (ref "P2") (pin "1") (pinfunction "1_1") (pintype "passive"))
      (node (ref "P3") (pin "2") (pinfunction "2_2") (pintype "passive"))
      (node (ref "P4") (pin "6") (pinfunction "6_6") (pintype "passive"))
      (node (ref "P5") (pin "2") (pinfunction "2_2") (pintype "passive"))
      (node (ref "P6") (pin "2") (pinfunction "2_2") (pintype "passive"))
      (node (ref "R14") (pin "2") (pinfunction "2_2") (pintype "passive"))
      (node (ref "R16") (pin "1") (pinfunction "1_1") (pintype "passive"))
      (node (ref "R17") (pin "1") (pinfunction "1_1") (pintype "passive"))
      (node (ref "R3") (pin "1") (pinfunction "1_1") (pintype "passive"))
      (node (ref "R4") (pin "1") (pinfunction "1_1") (pintype "passive"))
      (node (ref "R5") (pin "1") (pinfunction "1_1") (pintype "passive"))
      (node (ref "R7") (pin "2") (pinfunction "2_2") (pintype "passive"))
      (node (ref "R8") (pin "1") (pinfunction "1_1") (pintype "passive"))
      (node (ref "S1") (pin "3") (pinfunction "NO_1_3") (pintype "passive"))
      (node (ref "U1") (pin "11") (pinfunction "GND_11") (pintype "power_in"))
      (node (ref "U1") (pin "15") (pinfunction "GND_15") (pintype "power_in"))
      (node (ref "U1") (pin "17") (pinfunction "EP_17") (pintype "passive"))
      (node (ref "U1") (pin "3") (pinfunction "GND_3") (pintype "power_in"))
      (node (ref "U2") (pin "1") (pinfunction "CLKIN_1") (pintype "input"))
      (node (ref "U2") (pin "11") (pinfunction "FSYNC_11") (pintype "input"))
      (node (ref "U2") (pin "18") (pinfunction "GND_18") (pintype "power_in"))
      (node (ref "U2") (pin "9") (pinfunction "AD0_9") (pintype "input"))
      (node (ref "U3") (pin "11") (pinfunction "EP_11") (pintype "power_in"))
      (node (ref "U3") (pin "3") (pinfunction "VSS_3") (pintype "power_in"))
      (node (ref "U3") (pin "7") (pinfunction "ISET2_7") (pintype "passive"))
      (node (ref "U4") (pin "1") (pinfunction "GND1_1") (pintype "power_in"))
      (node (ref "U4") (pin "2") (pinfunction "GND1_2") (pintype "power_in"))
      (node (ref "U4") (pin "42") (pinfunction "GND1_42") (pintype "power_in"))
      (node (ref "U4") (pin "43") (pinfunction "GND1_43") (pintype "power_in"))
      (node (ref "U4") (pin "46") (pinfunction "GND1_46") (pintype "power_in"))
      (node (ref "U4") (pin "47") (pinfunction "GND1_47") (pintype "power_in"))
      (node (ref "U4") (pin "48") (pinfunction "GND1_48") (pintype "power_in"))
      (node (ref "U4") (pin "49") (pinfunction "GND1_49") (pintype "power_in"))
      (node (ref "U4") (pin "50") (pinfunction "GND1_50") (pintype "power_in"))
      (node (ref "U4") (pin "51") (pinfunction "GND1_51") (pintype "power_in"))
      (node (ref "U4") (pin "52") (pinfunction "GND1_52") (pintype "power_in"))
      (node (ref "U4") (pin "53") (pinfunction "GND1_53") (pintype "power_in"))
      (node (ref "U4") (pin "54") (pinfunction "GND2_54") (pintype "power_in"))
      (node (ref "U4") (pin "55") (pinfunction "GND2_55") (pintype "power_in"))
      (node (ref "U4") (pin "56") (pinfunction "GND2_56") (pintype "power_in"))
      (node (ref "U4") (pin "57") (pinfunction "GND2_57") (pintype "power_in"))
      (node (ref "U4") (pin "58") (pinfunction "GND2_58") (pintype "power_in"))
      (node (ref "U4") (pin "59") (pinfunction "GND2_59") (pintype "power_in"))
      (node (ref "U4") (pin "60") (pinfunction "GND3_60") (pintype "power_in"))
      (node (ref "U4") (pin "61_1") (pinfunction "GND3_61_1") (pintype "power_in"))
      (node (ref "U4") (pin "61_2") (pinfunction "GND3_61_2") (pintype "power_in"))
      (node (ref "U4") (pin "61_3") (pinfunction "GND3_61_3") (pintype "power_in"))
      (node (ref "U4") (pin "61_4") (pinfunction "GND3_61_4") (pintype "power_in"))
      (node (ref "U4") (pin "61_5") (pinfunction "GND3_61_5") (pintype "power_in"))
      (node (ref "U4") (pin "61_6") (pinfunction "GND3_61_6") (pintype "power_in"))
      (node (ref "U4") (pin "61_7") (pinfunction "GND3_61_7") (pintype "power_in"))
      (node (ref "U4") (pin "61_8") (pinfunction "GND3_61_8") (pintype "power_in"))
      (node (ref "U4") (pin "61_9") (pinfunction "GND3_61_9") (pintype "power_in"))
      (node (ref "U4") (pin "62") (pinfunction "GND2_62") (pintype "power_in"))
      (node (ref "U4") (pin "63") (pinfunction "GND2_63") (pintype "power_in"))
      (node (ref "U4") (pin "64") (pinfunction "GND2_64") (pintype "power_in"))
      (node (ref "U4") (pin "65") (pinfunction "GND2_65") (pintype "power_in"))
      (node (ref "U6") (pin "1") (pinfunction "GND_1") (pintype "power_in"))
    )
    (net (code "29") (name "Net-(C3-Pad2)") (class "Default")
      (node (ref "C3") (pin "2") (pinfunction "2_2") (pintype "passive"))
      (node (ref "C4") (pin "2") (pinfunction "2_2") (pintype "passive"))
      (node (ref "U1") (pin "7") (pinfunction "VDD_7") (pintype "power_in"))
      (node (ref "U1") (pin "8") (pinfunction "VDD_8") (pintype "power_in"))
    )
    (net (code "30") (name "Net-(C28-Pad1)") (class "Default")
      (node (ref "C28") (pin "1") (pinfunction "1_1") (pintype "passive"))
      (node (ref "R13") (pin "1") (pinfunction "1_1") (pintype "passive"))
    )
    (net (code "31") (name "Net-(IC2-FB)") (class "Default")
      (node (ref "C28") (pin "2") (pinfunction "2_2") (pintype "passive"))
      (node (ref "IC2") (pin "3") (pinfunction "FB_3") (pintype "passive"))
      (node (ref "R12") (pin "1") (pinfunction "1_1") (pintype "passive"))
      (node (ref "R14") (pin "1") (pinfunction "1_1") (pintype "passive"))
    )
    (net (code "32") (name "Net-(IC2-L1_1)") (class "Default")
      (node (ref "IC2") (pin "8") (pinfunction "L1_1_8") (pintype "passive"))
      (node (ref "IC2") (pin "9") (pinfunction "L1_2_9") (pintype "passive"))
      (node (ref "Y1") (pin "1") (pinfunction "1_1") (pintype "passive"))
    )
    (net (code "33") (name "Net-(IC2-L2_1)") (class "Default")
      (node (ref "IC2") (pin "6") (pinfunction "L2_1_6") (pintype "passive"))
      (node (ref "IC2") (pin "7") (pinfunction "L2_2_7") (pintype "passive"))
      (node (ref "Y1") (pin "2") (pinfunction "2_2") (pintype "passive"))
    )
    (net (code "34") (name "Net-(J1-CC1)") (class "Default")
      (node (ref "J1") (pin "A5") (pinfunction "CC1_A5") (pintype "power_in"))
      (node (ref "R5") (pin "2") (pinfunction "2_2") (pintype "passive"))
    )
    (net (code "35") (name "Net-(J1-CC2)") (class "Default")
      (node (ref "J1") (pin "B5") (pinfunction "CC2_B5") (pintype "power_in"))
      (node (ref "R7") (pin "1") (pinfunction "1_1") (pintype "passive"))
    )
    (net (code "36") (name "Net-(LED1-A)") (class "Default")
      (node (ref "LED1") (pin "2") (pinfunction "A_2") (pintype "passive"))
      (node (ref "R2") (pin "1") (pinfunction "1_1") (pintype "passive"))
    )
    (net (code "37") (name "Net-(LED1-K)") (class "Default")
      (node (ref "LED1") (pin "1") (pinfunction "K_1") (pintype "passive"))
      (node (ref "U3") (pin "5") (pinfunction "~{PG}_5") (pintype "tri_state"))
    )
    (net (code "38") (name "Net-(LED2-A)") (class "Default")
      (node (ref "LED2") (pin "2") (pinfunction "A_2") (pintype "passive"))
      (node (ref "R1") (pin "1") (pinfunction "1_1") (pintype "passive"))
    )
    (net (code "39") (name "Net-(LED2-K)") (class "Default")
      (node (ref "LED2") (pin "1") (pinfunction "K_1") (pintype "passive"))
      (node (ref "U3") (pin "8") (pinfunction "~{CHG}_8") (pintype "tri_state"))
    )
    (net (code "40") (name "Net-(U1-GAIN_SLOT)") (class "Default")
      (node (ref "R8") (pin "2") (pinfunction "2_2") (pintype "passive"))
      (node (ref "U1") (pin "2") (pinfunction "GAIN_SLOT_2") (pintype "passive"))
    )
    (net (code "41") (name "Net-(U1-OUTN)") (class "Default")
      (node (ref "P7") (pin "2") (pinfunction "2_2") (pintype "passive"))
      (node (ref "U1") (pin "10") (pinfunction "OUTN_10") (pintype "passive"))
    )
    (net (code "42") (name "Net-(U1-OUTP)") (class "Default")
      (node (ref "P7") (pin "1") (pinfunction "1_1") (pintype "passive"))
      (node (ref "U1") (pin "9") (pinfunction "OUTP_9") (pintype "passive"))
    )
    (net (code "43") (name "Net-(U1-~{SD_MODE})") (class "Default")
      (node (ref "R6") (pin "2") (pinfunction "2_2") (pintype "passive"))
      (node (ref "U1") (pin "4") (pinfunction "~{SD_MODE}_4") (pintype "input"))
    )
    (net (code "44") (name "Net-(U2-CPOUT)") (class "Default")
      (node (ref "C5") (pin "1") (pinfunction "1_1") (pintype "passive"))
      (node (ref "U2") (pin "20") (pinfunction "CPOUT_20") (pintype "passive"))
    )
    (net (code "45") (name "Net-(U2-REGOUT)") (class "Default")
      (node (ref "C7") (pin "2") (pinfunction "2_2") (pintype "passive"))
      (node (ref "U2") (pin "10") (pinfunction "REGOUT_10") (pintype "passive"))
    )
    (net (code "46") (name "Net-(U3-ISET)") (class "Default")
      (node (ref "R3") (pin "2") (pinfunction "2_2") (pintype "passive"))
      (node (ref "U3") (pin "2") (pinfunction "ISET_2") (pintype "input"))
    )
    (net (code "47") (name "Net-(U3-PRE-TERM)") (class "Default")
      (node (ref "R4") (pin "2") (pinfunction "2_2") (pintype "passive"))
      (node (ref "U3") (pin "4") (pinfunction "PRE-TERM_4") (pintype "passive"))
    )
    (net (code "48") (name "Net-(U3-TS)") (class "Default")
      (node (ref "R17") (pin "2") (pinfunction "2_2") (pintype "passive"))
      (node (ref "U3") (pin "9") (pinfunction "TS_9") (pintype "passive"))
    )
    (net (code "49") (name "unconnected-(IC2-PG-Pad14)") (class "Default")
      (node (ref "IC2") (pin "14") (pinfunction "PG_14") (pintype "passive"))
    )
    (net (code "50") (name "unconnected-(J1-SBU1-PadA8)") (class "Default")
      (node (ref "J1") (pin "A8") (pinfunction "SBU1_A8") (pintype "bidirectional"))
    )
    (net (code "51") (name "unconnected-(J1-SBU2-PadB8)") (class "Default")
      (node (ref "J1") (pin "B8") (pinfunction "SBU2_B8") (pintype "bidirectional"))
    )
    (net (code "52") (name "unconnected-(S1-COM_2-Pad2)") (class "Default")
      (node (ref "S1") (pin "2") (pinfunction "COM_2_2") (pintype "passive"))
    )
    (net (code "53") (name "unconnected-(S1-NO_2-Pad4)") (class "Default")
      (node (ref "S1") (pin "4") (pinfunction "NO_2_4") (pintype "passive"))
    )
    (net (code "54") (name "unconnected-(U1-NC-Pad5)") (class "Default")
      (node (ref "U1") (pin "5") (pinfunction "NC_5") (pintype "passive"))
    )
    (net (code "55") (name "unconnected-(U1-NC-Pad6)") (class "Default")
      (node (ref "U1") (pin "6") (pinfunction "NC_6") (pintype "passive"))
    )
    (net (code "56") (name "unconnected-(U1-NC-Pad12)") (class "Default")
      (node (ref "U1") (pin "12") (pinfunction "NC_12") (pintype "passive"))
    )
    (net (code "57") (name "unconnected-(U1-NC-Pad13)") (class "Default")
      (node (ref "U1") (pin "13") (pinfunction "NC_13") (pintype "passive"))
    )
    (net (code "58") (name "unconnected-(U2-AUX_CL-Pad7)") (class "Default")
      (node (ref "U2") (pin "7") (pinfunction "AUX_CL_7") (pintype "output"))
    )
    (net (code "59") (name "unconnected-(U2-AUX_DA-Pad6)") (class "Default")
      (node (ref "U2") (pin "6") (pinfunction "AUX_DA_6") (pintype "bidirectional"))
    )
    (net (code "60") (name "unconnected-(U2-CLKOUT-Pad22)") (class "Default")
      (node (ref "U2") (pin "22") (pinfunction "CLKOUT_22") (pintype "output"))
    )
    (net (code "61") (name "unconnected-(U2-EP-Pad25)") (class "Default")
      (node (ref "U2") (pin "25") (pinfunction "EP_25") (pintype "power_in"))
    )
    (net (code "62") (name "unconnected-(U2-INT-Pad12)") (class "Default")
      (node (ref "U2") (pin "12") (pinfunction "INT_12") (pintype "open_collector"))
    )
    (net (code "63") (name "unconnected-(U2-NC-Pad2)") (class "Default")
      (node (ref "U2") (pin "2") (pinfunction "NC_2") (pintype "passive"))
    )
    (net (code "64") (name "unconnected-(U2-NC-Pad3)") (class "Default")
      (node (ref "U2") (pin "3") (pinfunction "NC_3") (pintype "passive"))
    )
    (net (code "65") (name "unconnected-(U2-NC-Pad4)") (class "Default")
      (node (ref "U2") (pin "4") (pinfunction "NC_4") (pintype "passive"))
    )
    (net (code "66") (name "unconnected-(U2-NC-Pad5)") (class "Default")
      (node (ref "U2") (pin "5") (pinfunction "NC_5") (pintype "passive"))
    )
    (net (code "67") (name "unconnected-(U2-NC-Pad14)") (class "Default")
      (node (ref "U2") (pin "14") (pinfunction "NC_14") (pintype "passive"))
    )
    (net (code "68") (name "unconnected-(U2-NC-Pad15)") (class "Default")
      (node (ref "U2") (pin "15") (pinfunction "NC_15") (pintype "passive"))
    )
    (net (code "69") (name "unconnected-(U2-NC-Pad16)") (class "Default")
      (node (ref "U2") (pin "16") (pinfunction "NC_16") (pintype "passive"))
    )
    (net (code "70") (name "unconnected-(U2-NC-Pad17)") (class "Default")
      (node (ref "U2") (pin "17") (pinfunction "NC_17") (pintype "passive"))
    )
    (net (code "71") (name "unconnected-(U2-RESV-Pad19)") (class "Default")
      (node (ref "U2") (pin "19") (pinfunction "RESV_19") (pintype "passive"))
    )
    (net (code "72") (name "unconnected-(U2-RESV-Pad21)") (class "Default")
      (node (ref "U2") (pin "21") (pinfunction "RESV_21") (pintype "passive"))
    )
    (net (code "73") (name "unconnected-(U3-NC-Pad6)") (class "Default")
      (node (ref "U3") (pin "6") (pinfunction "NC_6") (pintype "passive"))
    )
    (net (code "74") (name "unconnected-(U4-IO1-Pad5)") (class "Default")
      (node (ref "U4") (pin "5") (pinfunction "IO1_5") (pintype "bidirectional"))
    )
    (net (code "75") (name "unconnected-(U4-IO2-Pad6)") (class "Default")
      (node (ref "U4") (pin "6") (pinfunction "IO2_6") (pintype "bidirectional"))
    )
    (net (code "76") (name "unconnected-(U4-IO3-Pad7)") (class "Default")
      (node (ref "U4") (pin "7") (pinfunction "IO3_7") (pintype "bidirectional"))
    )
    (net (code "77") (name "unconnected-(U4-IO17-Pad21)") (class "Default")
      (node (ref "U4") (pin "21") (pinfunction "IO17_21") (pintype "bidirectional"))
    )
    (net (code "78") (name "unconnected-(U4-IO18-Pad22)") (class "Default")
      (node (ref "U4") (pin "22") (pinfunction "IO18_22") (pintype "bidirectional"))
    )
    (net (code "79") (name "unconnected-(U4-IO21-Pad25)") (class "Default")
      (node (ref "U4") (pin "25") (pinfunction "IO21_25") (pintype "bidirectional"))
    )
    (net (code "80") (name "unconnected-(U4-IO26-Pad26)") (class "Default")
      (node (ref "U4") (pin "26") (pinfunction "IO26_26") (pintype "bidirectional"))
    )
    (net (code "81") (name "unconnected-(U4-IO39-Pad35)") (class "Default")
      (node (ref "U4") (pin "35") (pinfunction "IO39_35") (pintype "bidirectional"))
    )
    (net (code "82") (name "unconnected-(U4-IO40-Pad36)") (class "Default")
      (node (ref "U4") (pin "36") (pinfunction "IO40_36") (pintype "bidirectional"))
    )
    (net (code "83") (name "unconnected-(U4-IO41-Pad37)") (class "Default")
      (node (ref "U4") (pin "37") (pinfunction "IO41_37") (pintype "bidirectional"))
    )
    (net (code "84") (name "unconnected-(U4-IO42-Pad38)") (class "Default")
      (node (ref "U4") (pin "38") (pinfunction "IO42_38") (pintype "bidirectional"))
    )
    (net (code "85") (name "unconnected-(U4-IO45-Pad41)") (class "Default")
      (node (ref "U4") (pin "41") (pinfunction "IO45_41") (pintype "bidirectional"))
    )
    (net (code "86") (name "unconnected-(U4-IO46-Pad44)") (class "Default")
      (node (ref "U4") (pin "44") (pinfunction "IO46_44") (pintype "bidirectional"))
    )
    (net (code "87") (name "unconnected-(U4-IO47-Pad27)") (class "Default")
      (node (ref "U4") (pin "27") (pinfunction "IO47_27") (pintype "bidirectional"))
    )
    (net (code "88") (name "unconnected-(U4-IO48-Pad30)") (class "Default")
      (node (ref "U4") (pin "30") (pinfunction "IO48_30") (pintype "bidirectional"))
    )
    (net (code "89") (name "unconnected-(U4-RXD0-Pad40)") (class "Default")
      (node (ref "U4") (pin "40") (pinfunction "RXD0_40") (pintype "bidirectional"))
    )
    (net (code "90") (name "unconnected-(U4-TXD0-Pad39)") (class "Default")
      (node (ref "U4") (pin "39") (pinfunction "TXD0_39") (pintype "bidirectional"))
    )
  )
)
